# 2022_AESK_UAV_POWER.net
KiCad netlist of a schematic drawn in Altium Designer
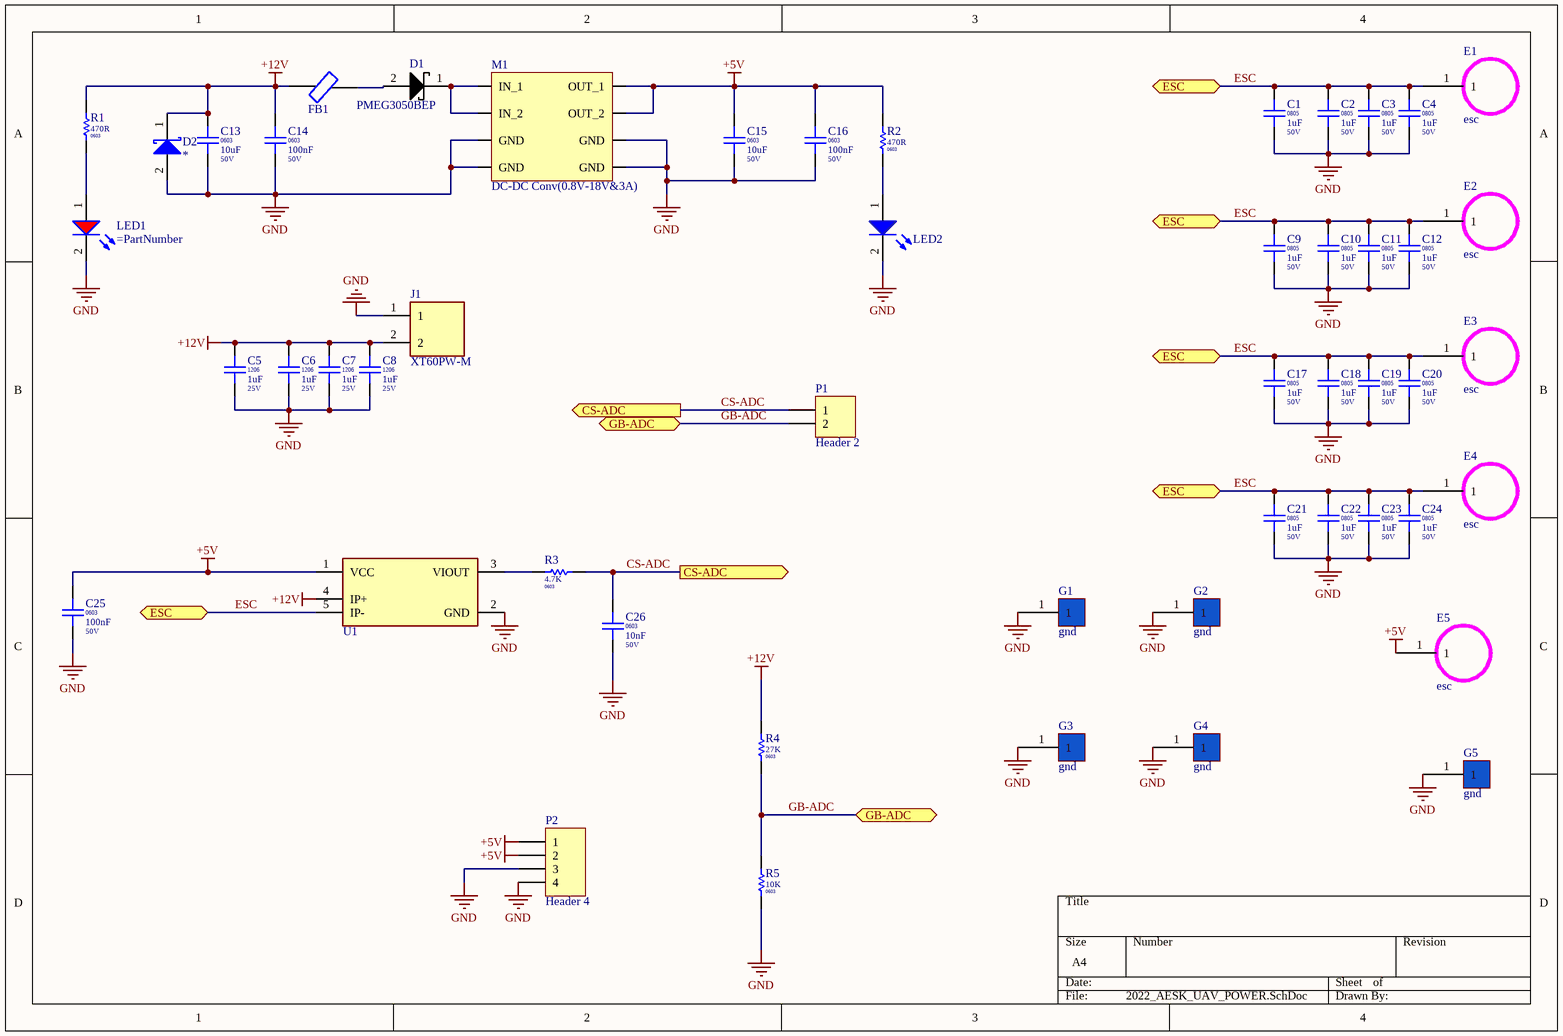
[diagram p0: 2022_AESK_UAV_POWER.SchDoc]

(export (version "E")
  (design (tool "Eeschema 10.0.6"))
  (components
    (comp (ref "C1")
      (value "1uF")
      (footprint "CAPC 0805")
      (description "Capacitor Ceramic 1uF 50V 0805")
      (fields
        (field (name "TOLERANCE") "%10")
        (field (name "PACKAGE / CASE") "0805")
        (field (name "VOLTAGE") "50V")
        (field (name "PART NUMBER") "CAPC0580")
      )
      (libsource (lib "AESK Database Library") (part "NPCapacitor"))
    )
    (comp (ref "C2")
      (value "1uF")
      (footprint "CAPC 0805")
      (description "Capacitor Ceramic 1uF 50V 0805")
      (fields
        (field (name "TOLERANCE") "%10")
        (field (name "PACKAGE / CASE") "0805")
        (field (name "VOLTAGE") "50V")
        (field (name "PART NUMBER") "CAPC0580")
      )
      (libsource (lib "AESK Database Library") (part "NPCapacitor"))
    )
    (comp (ref "C3")
      (value "1uF")
      (footprint "CAPC 0805")
      (description "Capacitor Ceramic 1uF 50V 0805")
      (fields
        (field (name "TOLERANCE") "%10")
        (field (name "PACKAGE / CASE") "0805")
        (field (name "VOLTAGE") "50V")
        (field (name "PART NUMBER") "CAPC0580")
      )
      (libsource (lib "AESK Database Library") (part "NPCapacitor"))
    )
    (comp (ref "C4")
      (value "1uF")
      (footprint "CAPC 0805")
      (description "Capacitor Ceramic 1uF 50V 0805")
      (fields
        (field (name "TOLERANCE") "%10")
        (field (name "PACKAGE / CASE") "0805")
        (field (name "VOLTAGE") "50V")
        (field (name "PART NUMBER") "CAPC0580")
      )
      (libsource (lib "AESK Database Library") (part "NPCapacitor"))
    )
    (comp (ref "C5")
      (value "1uF")
      (footprint "CAPC 1206")
      (description "Capacitor Ceramic 1uF 25V 1206")
      (fields
        (field (name "TOLERANCE") "%10")
        (field (name "PACKAGE / CASE") "1206")
        (field (name "VOLTAGE") "25V")
        (field (name "PART NUMBER") "CAPC0953")
      )
      (libsource (lib "AESK Database Library") (part "NPCapacitor"))
    )
    (comp (ref "C6")
      (value "1uF")
      (footprint "CAPC 1206")
      (description "Capacitor Ceramic 1uF 25V 1206")
      (fields
        (field (name "TOLERANCE") "%10")
        (field (name "PACKAGE / CASE") "1206")
        (field (name "VOLTAGE") "25V")
        (field (name "PART NUMBER") "CAPC0953")
      )
      (libsource (lib "AESK Database Library") (part "NPCapacitor"))
    )
    (comp (ref "C7")
      (value "1uF")
      (footprint "CAPC 1206")
      (description "Capacitor Ceramic 1uF 25V 1206")
      (fields
        (field (name "TOLERANCE") "%10")
        (field (name "PACKAGE / CASE") "1206")
        (field (name "VOLTAGE") "25V")
        (field (name "PART NUMBER") "CAPC0953")
      )
      (libsource (lib "AESK Database Library") (part "NPCapacitor"))
    )
    (comp (ref "C8")
      (value "1uF")
      (footprint "CAPC 1206")
      (description "Capacitor Ceramic 1uF 25V 1206")
      (fields
        (field (name "TOLERANCE") "%10")
        (field (name "PACKAGE / CASE") "1206")
        (field (name "VOLTAGE") "25V")
        (field (name "PART NUMBER") "CAPC0953")
      )
      (libsource (lib "AESK Database Library") (part "NPCapacitor"))
    )
    (comp (ref "C9")
      (value "1uF")
      (footprint "CAPC 0805")
      (description "Capacitor Ceramic 1uF 50V 0805")
      (fields
        (field (name "TOLERANCE") "%10")
        (field (name "PACKAGE / CASE") "0805")
        (field (name "VOLTAGE") "50V")
        (field (name "PART NUMBER") "CAPC0580")
      )
      (libsource (lib "AESK Database Library") (part "NPCapacitor"))
    )
    (comp (ref "C10")
      (value "1uF")
      (footprint "CAPC 0805")
      (description "Capacitor Ceramic 1uF 50V 0805")
      (fields
        (field (name "TOLERANCE") "%10")
        (field (name "PACKAGE / CASE") "0805")
        (field (name "VOLTAGE") "50V")
        (field (name "PART NUMBER") "CAPC0580")
      )
      (libsource (lib "AESK Database Library") (part "NPCapacitor"))
    )
    (comp (ref "C11")
      (value "1uF")
      (footprint "CAPC 0805")
      (description "Capacitor Ceramic 1uF 50V 0805")
      (fields
        (field (name "TOLERANCE") "%10")
        (field (name "PACKAGE / CASE") "0805")
        (field (name "VOLTAGE") "50V")
        (field (name "PART NUMBER") "CAPC0580")
      )
      (libsource (lib "AESK Database Library") (part "NPCapacitor"))
    )
    (comp (ref "C12")
      (value "1uF")
      (footprint "CAPC 0805")
      (description "Capacitor Ceramic 1uF 50V 0805")
      (fields
        (field (name "TOLERANCE") "%10")
        (field (name "PACKAGE / CASE") "0805")
        (field (name "VOLTAGE") "50V")
        (field (name "PART NUMBER") "CAPC0580")
      )
      (libsource (lib "AESK Database Library") (part "NPCapacitor"))
    )
    (comp (ref "C13")
      (value "10uF")
      (footprint "CAPC 0603")
      (description "Capacitor Ceramic 10uF 50V 0603")
      (fields
        (field (name "TOLERANCE") "%10")
        (field (name "PACKAGE / CASE") "0603")
        (field (name "VOLTAGE") "50V")
        (field (name "PART NUMBER") "CAPC0301")
      )
      (libsource (lib "AESK Database Library") (part "NPCapacitor"))
    )
    (comp (ref "C14")
      (value "100nF")
      (footprint "CAPC 0603")
      (description "Capacitor Ceramic 100nF 50V 0603")
      (fields
        (field (name "TOLERANCE") "%10")
        (field (name "PACKAGE / CASE") "0603")
        (field (name "VOLTAGE") "50V")
        (field (name "PART NUMBER") "CAPC0285")
      )
      (libsource (lib "AESK Database Library") (part "NPCapacitor"))
    )
    (comp (ref "C15")
      (value "10uF")
      (footprint "CAPC 0603")
      (description "Capacitor Ceramic 10uF 50V 0603")
      (fields
        (field (name "TOLERANCE") "%10")
        (field (name "PACKAGE / CASE") "0603")
        (field (name "VOLTAGE") "50V")
        (field (name "PART NUMBER") "CAPC0301")
      )
      (libsource (lib "AESK Database Library") (part "NPCapacitor"))
    )
    (comp (ref "C16")
      (value "100nF")
      (footprint "CAPC 0603")
      (description "Capacitor Ceramic 100nF 50V 0603")
      (fields
        (field (name "TOLERANCE") "%10")
        (field (name "PACKAGE / CASE") "0603")
        (field (name "VOLTAGE") "50V")
        (field (name "PART NUMBER") "CAPC0285")
      )
      (libsource (lib "AESK Database Library") (part "NPCapacitor"))
    )
    (comp (ref "C17")
      (value "1uF")
      (footprint "CAPC 0805")
      (description "Capacitor Ceramic 1uF 50V 0805")
      (fields
        (field (name "TOLERANCE") "%10")
        (field (name "PACKAGE / CASE") "0805")
        (field (name "VOLTAGE") "50V")
        (field (name "PART NUMBER") "CAPC0580")
      )
      (libsource (lib "AESK Database Library") (part "NPCapacitor"))
    )
    (comp (ref "C18")
      (value "1uF")
      (footprint "CAPC 0805")
      (description "Capacitor Ceramic 1uF 50V 0805")
      (fields
        (field (name "TOLERANCE") "%10")
        (field (name "PACKAGE / CASE") "0805")
        (field (name "VOLTAGE") "50V")
        (field (name "PART NUMBER") "CAPC0580")
      )
      (libsource (lib "AESK Database Library") (part "NPCapacitor"))
    )
    (comp (ref "C19")
      (value "1uF")
      (footprint "CAPC 0805")
      (description "Capacitor Ceramic 1uF 50V 0805")
      (fields
        (field (name "TOLERANCE") "%10")
        (field (name "PACKAGE / CASE") "0805")
        (field (name "VOLTAGE") "50V")
        (field (name "PART NUMBER") "CAPC0580")
      )
      (libsource (lib "AESK Database Library") (part "NPCapacitor"))
    )
    (comp (ref "C20")
      (value "1uF")
      (footprint "CAPC 0805")
      (description "Capacitor Ceramic 1uF 50V 0805")
      (fields
        (field (name "TOLERANCE") "%10")
        (field (name "PACKAGE / CASE") "0805")
        (field (name "VOLTAGE") "50V")
        (field (name "PART NUMBER") "CAPC0580")
      )
      (libsource (lib "AESK Database Library") (part "NPCapacitor"))
    )
    (comp (ref "C21")
      (value "1uF")
      (footprint "CAPC 0805")
      (description "Capacitor Ceramic 1uF 50V 0805")
      (fields
        (field (name "TOLERANCE") "%10")
        (field (name "PACKAGE / CASE") "0805")
        (field (name "VOLTAGE") "50V")
        (field (name "PART NUMBER") "CAPC0580")
      )
      (libsource (lib "AESK Database Library") (part "NPCapacitor"))
    )
    (comp (ref "C22")
      (value "1uF")
      (footprint "CAPC 0805")
      (description "Capacitor Ceramic 1uF 50V 0805")
      (fields
        (field (name "TOLERANCE") "%10")
        (field (name "PACKAGE / CASE") "0805")
        (field (name "VOLTAGE") "50V")
        (field (name "PART NUMBER") "CAPC0580")
      )
      (libsource (lib "AESK Database Library") (part "NPCapacitor"))
    )
    (comp (ref "C23")
      (value "1uF")
      (footprint "CAPC 0805")
      (description "Capacitor Ceramic 1uF 50V 0805")
      (fields
        (field (name "TOLERANCE") "%10")
        (field (name "PACKAGE / CASE") "0805")
        (field (name "VOLTAGE") "50V")
        (field (name "PART NUMBER") "CAPC0580")
      )
      (libsource (lib "AESK Database Library") (part "NPCapacitor"))
    )
    (comp (ref "C24")
      (value "1uF")
      (footprint "CAPC 0805")
      (description "Capacitor Ceramic 1uF 50V 0805")
      (fields
        (field (name "TOLERANCE") "%10")
        (field (name "PACKAGE / CASE") "0805")
        (field (name "VOLTAGE") "50V")
        (field (name "PART NUMBER") "CAPC0580")
      )
      (libsource (lib "AESK Database Library") (part "NPCapacitor"))
    )
    (comp (ref "C25")
      (value "100nF")
      (footprint "CAPC 0603")
      (description "Capacitor Ceramic 100nF 50V 0603")
      (fields
        (field (name "TOLERANCE") "%10")
        (field (name "PACKAGE / CASE") "0603")
        (field (name "VOLTAGE") "50V")
        (field (name "PART NUMBER") "CAPC0285")
      )
      (libsource (lib "AESK Database Library") (part "NPCapacitor"))
    )
    (comp (ref "C26")
      (value "10nF")
      (footprint "CAPC 0603")
      (description "Capacitor Ceramic 10nF 50V 0603")
      (fields
        (field (name "TOLERANCE") "%10")
        (field (name "PACKAGE / CASE") "0603")
        (field (name "VOLTAGE") "50V")
        (field (name "PART NUMBER") "CAPC0277")
      )
      (libsource (lib "AESK Database Library") (part "NPCapacitor"))
    )
    (comp (ref "D1")
      (value "PMEG3050BEP")
      (footprint "SOD470X100-2N")
      (description "Schotky Diode")
      (fields
        (field (name "MANUFACTURER") "Nexperia USA")
        (field (name "MANUFACTURER PART NUMBER") "PMEG3050BEP,115")
      )
      (libsource (lib "2022_AESK_UAV_POWER") (part "Schotky Diode"))
    )
    (comp (ref "D2")
      (value "*")
      (footprint "DO-214AC, SMA")
      (fields (field (name "PART NUMBER") "Diode0012"))
      (libsource (lib "AESK Database Library") (part "Schottky Diode"))
    )
    (comp (ref "E1") (value "esc") (footprint "esc") (libsource (lib "2022_AESK_UAV_POWER") (part "esc")))
    (comp (ref "E2") (value "esc") (footprint "esc") (libsource (lib "2022_AESK_UAV_POWER") (part "esc")))
    (comp (ref "E3") (value "esc") (footprint "esc") (libsource (lib "2022_AESK_UAV_POWER") (part "esc")))
    (comp (ref "E4") (value "esc") (footprint "esc") (libsource (lib "2022_AESK_UAV_POWER") (part "esc")))
    (comp (ref "E5") (value "esc") (footprint "esc") (libsource (lib "2022_AESK_UAV_POWER") (part "esc")))
    (comp (ref "FB1")
      (value "Ferrite Bead")
      (footprint "FCM1608KF-601T03")
      (libsource (lib "2022_AESK_UAV_POWER") (part "FCM1608KF-601T03"))
    )
    (comp (ref "G1") (value "gnd") (footprint "gnd") (libsource (lib "2022_AESK_UAV_POWER") (part "gnd")))
    (comp (ref "G2") (value "gnd") (footprint "gnd") (libsource (lib "2022_AESK_UAV_POWER") (part "gnd")))
    (comp (ref "G3") (value "gnd") (footprint "gnd") (libsource (lib "2022_AESK_UAV_POWER") (part "gnd")))
    (comp (ref "G4") (value "gnd") (footprint "gnd") (libsource (lib "2022_AESK_UAV_POWER") (part "gnd")))
    (comp (ref "G5") (value "gnd") (footprint "gnd") (libsource (lib "2022_AESK_UAV_POWER") (part "gnd")))
    (comp (ref "J1")
      (value "XT60PW-M")
      (footprint "AMASS_XT60PW-M")
      (fields (field (name "MF") "AMASS"))
      (libsource (lib "UAV_POWER") (part "XT60PW-M"))
    )
    (comp (ref "LED1")
      (value "~")
      (footprint "LED RED 0603")
      (description "LED")
      (libsource (lib "Diodes_GESK") (part "LED RED"))
    )
    (comp (ref "LED2")
      (value "~")
      (footprint "LED BLUE 0603")
      (description "LED")
      (libsource (lib "Diodes_GESK") (part "LED BLUE"))
    )
    (comp (ref "M1")
      (value "DC-DC Conv(0.8V-18V&3A)")
      (footprint "mp")
      (libsource (lib "UAV_UcusKontrolKartı_Sematik_Kutuphane") (part "MP1584EN"))
    )
    (comp (ref "P1")
      (value "Header 2")
      (footprint "HDR1X2")
      (description "Header, 2-Pin")
      (fields (field (name "PUBLISHER") "Altium Limited"))
      (libsource (lib "Miscellaneous Connectors") (part "Header 2"))
    )
    (comp (ref "P2")
      (value "Header 4")
      (footprint "HDR1X4")
      (description "Header, 4-Pin")
      (fields (field (name "PUBLISHER") "Altium Limited"))
      (libsource (lib "Miscellaneous Connectors") (part "Header 4"))
    )
    (comp (ref "R1")
      (value "470R")
      (footprint "RESC 0603")
      (description "470R 0603")
      (fields
        (field (name "TOLERANCE") "%5")
        (field (name "POWER") "1/10W")
        (field (name "PACKAGE / CASE") "0603")
      )
      (libsource (lib "AESK Database Library") (part "Resistor"))
    )
    (comp (ref "R2")
      (value "470R")
      (footprint "RESC 0603")
      (description "470R 0603")
      (fields
        (field (name "TOLERANCE") "%5")
        (field (name "POWER") "1/10W")
        (field (name "PACKAGE / CASE") "0603")
      )
      (libsource (lib "AESK Database Library") (part "Resistor"))
    )
    (comp (ref "R3")
      (value "4.7K")
      (footprint "RESC 0603")
      (description "4.7K 0603")
      (fields
        (field (name "TOLERANCE") "%5")
        (field (name "POWER") "1/10W")
        (field (name "PACKAGE / CASE") "0603")
      )
      (libsource (lib "AESK Database Library") (part "Resistor"))
    )
    (comp (ref "R4")
      (value "27K")
      (footprint "RESC 0603")
      (description "27K 0603")
      (fields
        (field (name "TOLERANCE") "%5")
        (field (name "POWER") "1/10W")
        (field (name "PACKAGE / CASE") "0603")
      )
      (libsource (lib "AESK Database Library") (part "Resistor"))
    )
    (comp (ref "R5")
      (value "10K")
      (footprint "RESC 0603")
      (description "10K 0603")
      (fields
        (field (name "TOLERANCE") "%5")
        (field (name "POWER") "1/10W")
        (field (name "PACKAGE / CASE") "0603")
      )
      (libsource (lib "AESK Database Library") (part "Resistor"))
    )
    (comp (ref "U1")
      (value "ACS758KCB-150B-PFF-T")
      (footprint "Allegro_MicroSystems_LLC_CB-5-PFF_MFG")
      (libsource (lib "2022_AESK_UAV_POWER") (part "ACS758KCB-150B-PFF-T"))
    )
  )
  (nets
    (net (code "1") (name "+5V") (class "Default")
      (node (ref "C15") (pin "2") (pinfunction "2_2") (pintype "passive"))
      (node (ref "C16") (pin "2") (pinfunction "2_2") (pintype "passive"))
      (node (ref "C25") (pin "2") (pinfunction "2_2") (pintype "passive"))
      (node (ref "E5") (pin "1") (pinfunction "1_1") (pintype "passive"))
      (node (ref "M1") (pin "3") (pinfunction "OUT_1_3") (pintype "passive"))
      (node (ref "M1") (pin "4") (pinfunction "OUT_2_4") (pintype "passive"))
      (node (ref "P2") (pin "1") (pinfunction "1_1") (pintype "passive"))
      (node (ref "P2") (pin "2") (pinfunction "2_2") (pintype "passive"))
      (node (ref "R2") (pin "2") (pinfunction "2_2") (pintype "passive"))
      (node (ref "U1") (pin "1") (pinfunction "VCC_1") (pintype "power_in"))
    )
    (net (code "2") (name "+12V") (class "Default")
      (node (ref "C13") (pin "2") (pinfunction "2_2") (pintype "passive"))
      (node (ref "C14") (pin "2") (pinfunction "2_2") (pintype "passive"))
      (node (ref "C5") (pin "2") (pinfunction "2_2") (pintype "passive"))
      (node (ref "C6") (pin "2") (pinfunction "2_2") (pintype "passive"))
      (node (ref "C7") (pin "2") (pinfunction "2_2") (pintype "passive"))
      (node (ref "C8") (pin "2") (pinfunction "2_2") (pintype "passive"))
      (node (ref "D2") (pin "1") (pinfunction "K_1") (pintype "passive"))
      (node (ref "FB1") (pin "1") (pinfunction "1_1") (pintype "passive"))
      (node (ref "J1") (pin "2") (pinfunction "2_2") (pintype "passive"))
      (node (ref "R1") (pin "2") (pinfunction "2_2") (pintype "passive"))
      (node (ref "R4") (pin "2") (pinfunction "2_2") (pintype "passive"))
      (node (ref "U1") (pin "4") (pinfunction "IP+_4") (pintype "passive"))
    )
    (net (code "3") (name "/CS-ADC") (class "Default")
      (node (ref "C26") (pin "2") (pinfunction "2_2") (pintype "passive"))
      (node (ref "P1") (pin "1") (pinfunction "1_1") (pintype "passive"))
      (node (ref "R3") (pin "1") (pinfunction "1_1") (pintype "passive"))
    )
    (net (code "4") (name "/ESC") (class "Default")
      (node (ref "C1") (pin "2") (pinfunction "2_2") (pintype "passive"))
      (node (ref "C10") (pin "2") (pinfunction "2_2") (pintype "passive"))
      (node (ref "C11") (pin "2") (pinfunction "2_2") (pintype "passive"))
      (node (ref "C12") (pin "2") (pinfunction "2_2") (pintype "passive"))
      (node (ref "C17") (pin "2") (pinfunction "2_2") (pintype "passive"))
      (node (ref "C18") (pin "2") (pinfunction "2_2") (pintype "passive"))
      (node (ref "C19") (pin "2") (pinfunction "2_2") (pintype "passive"))
      (node (ref "C2") (pin "2") (pinfunction "2_2") (pintype "passive"))
      (node (ref "C20") (pin "2") (pinfunction "2_2") (pintype "passive"))
      (node (ref "C21") (pin "2") (pinfunction "2_2") (pintype "passive"))
      (node (ref "C22") (pin "2") (pinfunction "2_2") (pintype "passive"))
      (node (ref "C23") (pin "2") (pinfunction "2_2") (pintype "passive"))
      (node (ref "C24") (pin "2") (pinfunction "2_2") (pintype "passive"))
      (node (ref "C3") (pin "2") (pinfunction "2_2") (pintype "passive"))
      (node (ref "C4") (pin "2") (pinfunction "2_2") (pintype "passive"))
      (node (ref "C9") (pin "2") (pinfunction "2_2") (pintype "passive"))
      (node (ref "E1") (pin "1") (pinfunction "1_1") (pintype "passive"))
      (node (ref "E2") (pin "1") (pinfunction "1_1") (pintype "passive"))
      (node (ref "E3") (pin "1") (pinfunction "1_1") (pintype "passive"))
      (node (ref "E4") (pin "1") (pinfunction "1_1") (pintype "passive"))
      (node (ref "U1") (pin "5") (pinfunction "IP-_5") (pintype "passive"))
    )
    (net (code "5") (name "/GB-ADC") (class "Default")
      (node (ref "P1") (pin "2") (pinfunction "2_2") (pintype "passive"))
      (node (ref "R4") (pin "1") (pinfunction "1_1") (pintype "passive"))
      (node (ref "R5") (pin "2") (pinfunction "2_2") (pintype "passive"))
    )
    (net (code "6") (name "GND") (class "Default")
      (node (ref "C1") (pin "1") (pinfunction "1_1") (pintype "passive"))
      (node (ref "C10") (pin "1") (pinfunction "1_1") (pintype "passive"))
      (node (ref "C11") (pin "1") (pinfunction "1_1") (pintype "passive"))
      (node (ref "C12") (pin "1") (pinfunction "1_1") (pintype "passive"))
      (node (ref "C13") (pin "1") (pinfunction "1_1") (pintype "passive"))
      (node (ref "C14") (pin "1") (pinfunction "1_1") (pintype "passive"))
      (node (ref "C15") (pin "1") (pinfunction "1_1") (pintype "passive"))
      (node (ref "C16") (pin "1") (pinfunction "1_1") (pintype "passive"))
      (node (ref "C17") (pin "1") (pinfunction "1_1") (pintype "passive"))
      (node (ref "C18") (pin "1") (pinfunction "1_1") (pintype "passive"))
      (node (ref "C19") (pin "1") (pinfunction "1_1") (pintype "passive"))
      (node (ref "C2") (pin "1") (pinfunction "1_1") (pintype "passive"))
      (node (ref "C20") (pin "1") (pinfunction "1_1") (pintype "passive"))
      (node (ref "C21") (pin "1") (pinfunction "1_1") (pintype "passive"))
      (node (ref "C22") (pin "1") (pinfunction "1_1") (pintype "passive"))
      (node (ref "C23") (pin "1") (pinfunction "1_1") (pintype "passive"))
      (node (ref "C24") (pin "1") (pinfunction "1_1") (pintype "passive"))
      (node (ref "C25") (pin "1") (pinfunction "1_1") (pintype "passive"))
      (node (ref "C26") (pin "1") (pinfunction "1_1") (pintype "passive"))
      (node (ref "C3") (pin "1") (pinfunction "1_1") (pintype "passive"))
      (node (ref "C4") (pin "1") (pinfunction "1_1") (pintype "passive"))
      (node (ref "C5") (pin "1") (pinfunction "1_1") (pintype "passive"))
      (node (ref "C6") (pin "1") (pinfunction "1_1") (pintype "passive"))
      (node (ref "C7") (pin "1") (pinfunction "1_1") (pintype "passive"))
      (node (ref "C8") (pin "1") (pinfunction "1_1") (pintype "passive"))
      (node (ref "C9") (pin "1") (pinfunction "1_1") (pintype "passive"))
      (node (ref "D2") (pin "2") (pinfunction "A_2") (pintype "passive"))
      (node (ref "G1") (pin "1") (pinfunction "1_1") (pintype "passive"))
      (node (ref "G2") (pin "1") (pinfunction "1_1") (pintype "passive"))
      (node (ref "G3") (pin "1") (pinfunction "1_1") (pintype "passive"))
      (node (ref "G4") (pin "1") (pinfunction "1_1") (pintype "passive"))
      (node (ref "G5") (pin "1") (pinfunction "1_1") (pintype "passive"))
      (node (ref "J1") (pin "1") (pinfunction "1_1") (pintype "passive"))
      (node (ref "LED1") (pin "2") (pinfunction "C_2") (pintype "passive"))
      (node (ref "LED2") (pin "2") (pinfunction "C_2") (pintype "passive"))
      (node (ref "M1") (pin "5") (pinfunction "GND_5") (pintype "passive"))
      (node (ref "M1") (pin "6") (pinfunction "GND_6") (pintype "passive"))
      (node (ref "M1") (pin "7") (pinfunction "GND_7") (pintype "passive"))
      (node (ref "M1") (pin "8") (pinfunction "GND_8") (pintype "passive"))
      (node (ref "P2") (pin "3") (pinfunction "3_3") (pintype "passive"))
      (node (ref "P2") (pin "4") (pinfunction "4_4") (pintype "passive"))
      (node (ref "R5") (pin "1") (pinfunction "1_1") (pintype "passive"))
      (node (ref "U1") (pin "2") (pinfunction "GND_2") (pintype "power_in"))
    )
    (net (code "7") (name "Net-(D1-A)") (class "Default")
      (node (ref "D1") (pin "2") (pinfunction "A_2") (pintype "passive"))
      (node (ref "FB1") (pin "2") (pinfunction "2_2") (pintype "passive"))
    )
    (net (code "8") (name "Net-(D1-K)") (class "Default")
      (node (ref "D1") (pin "1") (pinfunction "K_1") (pintype "passive"))
      (node (ref "M1") (pin "1") (pinfunction "IN_1_1") (pintype "passive"))
      (node (ref "M1") (pin "2") (pinfunction "IN_2_2") (pintype "passive"))
    )
    (net (code "9") (name "Net-(LED1-A)") (class "Default")
      (node (ref "LED1") (pin "1") (pinfunction "A_1") (pintype "passive"))
      (node (ref "R1") (pin "1") (pinfunction "1_1") (pintype "passive"))
    )
    (net (code "10") (name "Net-(LED2-A)") (class "Default")
      (node (ref "LED2") (pin "1") (pinfunction "A_1") (pintype "passive"))
      (node (ref "R2") (pin "1") (pinfunction "1_1") (pintype "passive"))
    )
    (net (code "11") (name "Net-(U1-VIOUT)") (class "Default")
      (node (ref "R3") (pin "2") (pinfunction "2_2") (pintype "passive"))
      (node (ref "U1") (pin "3") (pinfunction "VIOUT_3") (pintype "passive"))
    )
  )
)
